# IOs_DMX8x8A.net
KiCad netlist of a schematic drawn in Altium Designer
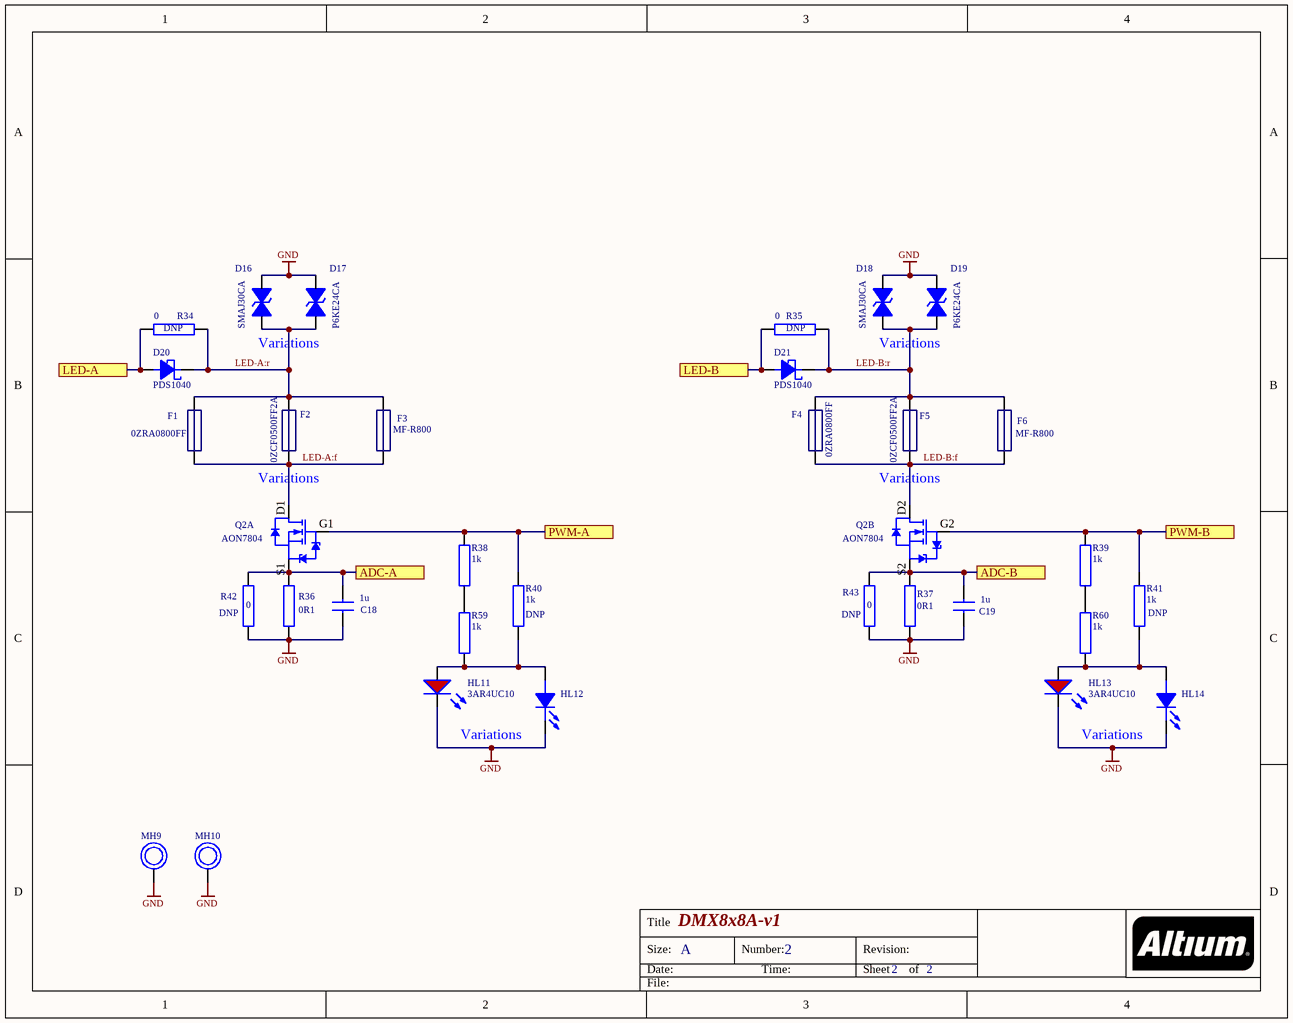
[diagram p0: IOs.DMX8x8A.SchDoc]

(export (version "E")
  (design (tool "Eeschema 10.0.6"))
  (components
    (comp (ref "C18")
      (value "1u")
      (footprint "Chip C 0402 - 1206")
      (description "Ceramic Chip Capacitor")
      (fields (field (name "Comment") "1u 50V 5%"))
      (libsource (lib "Capacitors") (part "Ceramic SMD Cap_R"))
    )
    (comp (ref "C19")
      (value "1u")
      (footprint "Chip C 0402 - 1206")
      (description "Ceramic Chip Capacitor")
      (fields (field (name "Comment") "1u 50V 5%"))
      (libsource (lib "Capacitors") (part "Ceramic SMD Cap_R"))
    )
    (comp (ref "D16")
      (value "SMAJ30CA")
      (footprint "DO-214AC (SMA) biplar")
      (description "TVS Uni 30V")
      (fields (field (name "MFR") "ST"))
      (libsource (lib "TVS") (part "SMAJ30CA"))
    )
    (comp (ref "D17")
      (value "P6KE24CA")
      (footprint "DIOAD1910W90L670D310 (DO-15)")
      (description "TVS Axial 600W Unipolar 24V")
      (libsource (lib "DMX512") (part "P6KE"))
    )
    (comp (ref "D18")
      (value "SMAJ30CA")
      (footprint "DO-214AC (SMA) biplar")
      (description "TVS Uni 30V")
      (fields (field (name "MFR") "ST"))
      (libsource (lib "TVS") (part "SMAJ30CA"))
    )
    (comp (ref "D19")
      (value "P6KE24CA")
      (footprint "DIOAD1910W90L670D310 (DO-15)")
      (description "TVS Axial 600W Unipolar 24V")
      (libsource (lib "DMX512") (part "P6KE"))
    )
    (comp (ref "D20")
      (value "PDS1040")
      (footprint "PDS1040")
      (description "10A SCHOTTKY BARRIER RECTIFIER")
      (fields (field (name "MFR") "DIODES INC."))
      (libsource (lib "Diodes") (part "PDS1040"))
    )
    (comp (ref "D21")
      (value "PDS1040")
      (footprint "PDS1040")
      (description "10A SCHOTTKY BARRIER RECTIFIER")
      (fields (field (name "MFR") "DIODES INC."))
      (libsource (lib "Diodes") (part "PDS1040"))
    )
    (comp (ref "F1")
      (value "0ZRA0800FF")
      (footprint "0ZRA0800FF")
      (description "Radial Leaded PTC 8/13.6A")
      (libsource (lib "DMX512") (part "0ZRA"))
    )
    (comp (ref "F2")
      (value "0ZCF0500FF2A")
      (footprint "0ZCF0500FF2A")
      (description "Surface Mount PTC 5/10A")
      (libsource (lib "DMX512") (part "0ZCF0500FF2A"))
    )
    (comp (ref "F3")
      (value "MF-R800")
      (footprint "MF-R800")
      (description "PTC Resettable Fuse 8/16A")
      (libsource (lib "DMX512") (part "MF-R800"))
    )
    (comp (ref "F4")
      (value "0ZRA0800FF")
      (footprint "0ZRA0800FF")
      (description "Radial Leaded PTC 8/13.6A")
      (libsource (lib "DMX512") (part "0ZRA"))
    )
    (comp (ref "F5")
      (value "0ZCF0500FF2A")
      (footprint "0ZCF0500FF2A")
      (description "Surface Mount PTC 5/10A")
      (libsource (lib "DMX512") (part "0ZCF0500FF2A"))
    )
    (comp (ref "F6")
      (value "MF-R800")
      (footprint "MF-R800")
      (description "PTC Resettable Fuse 8/16A")
      (libsource (lib "DMX512") (part "MF-R800"))
    )
    (comp (ref "HL11")
      (value "3AR4UC10")
      (footprint "LED-2pin 2.54mm")
      (description "LED 3mm Red")
      (libsource (lib "DMX512") (part "3AR4UC10"))
    )
    (comp (ref "HL12")
      (value "? Any")
      (footprint "LED SMD 0805")
      (description "LED 0805")
      (libsource (lib "DMX512") (part "LED 0805"))
    )
    (comp (ref "HL13")
      (value "3AR4UC10")
      (footprint "LED-2pin 2.54mm")
      (description "LED 3mm Red")
      (libsource (lib "DMX512") (part "3AR4UC10"))
    )
    (comp (ref "HL14")
      (value "? Any")
      (footprint "LED SMD 0805")
      (description "LED 0805")
      (libsource (lib "DMX512") (part "LED 0805"))
    )
    (comp (ref "MH9")
      (value "PMH")
      (footprint "Hole Pad 3.2x4mm")
      (description "Plated Mounting Hole")
      (libsource (lib "Misc") (part "PMH"))
    )
    (comp (ref "MH10")
      (value "PMH")
      (footprint "Hole Pad 3.2x4mm")
      (description "Plated Mounting Hole")
      (libsource (lib "Misc") (part "PMH"))
    )
    (comp (ref "Q2")
      (value "AON7804")
      (footprint "AON7804")
      (description "30V Dual N-Channel MOSFET")
      (libsource (lib "DMX512") (part "AON7804"))
    )
    (comp (ref "R34")
      (value "0")
      (footprint "Chip R 0402 - 1206")
      (description "Chip Resistor")
      (fields (field (name "DNP") "DNP") (field (name "Comment") "0 5%"))
      (libsource (lib "Resistors") (part "Chip R"))
    )
    (comp (ref "R35")
      (value "0")
      (footprint "Chip R 0402 - 1206")
      (description "Chip Resistor")
      (fields (field (name "DNP") "DNP") (field (name "Comment") "0 5%"))
      (libsource (lib "Resistors") (part "Chip R"))
    )
    (comp (ref "R36")
      (value "0R1")
      (footprint "DMX512:RES7W")
      (description "Resistor 7W Axial")
      (fields (field (name "MFR") "Yageo") (field (name "Comment") "KNP700JB-91-0R1"))
      (libsource (lib "DMX512") (part "Res 7W"))
    )
    (comp (ref "R37")
      (value "0R1")
      (footprint "DMX512:RES7W")
      (description "Resistor 7W Axial")
      (fields (field (name "MFR") "Yageo") (field (name "Comment") "KNP700JB-91-0R1"))
      (libsource (lib "DMX512") (part "Res 7W"))
    )
    (comp (ref "R38")
      (value "1k")
      (footprint "Chip R 0402 - 1206")
      (description "Chip Resistor")
      (fields (field (name "Comment") "1k 5%"))
      (libsource (lib "Resistors") (part "Chip R"))
    )
    (comp (ref "R39")
      (value "1k")
      (footprint "Chip R 0402 - 1206")
      (description "Chip Resistor")
      (fields (field (name "Comment") "1k 5%"))
      (libsource (lib "Resistors") (part "Chip R"))
    )
    (comp (ref "R40")
      (value "1k")
      (footprint "Chip R 0402 - 1206")
      (description "Chip Resistor")
      (fields (field (name "DNP") "DNP") (field (name "Comment") "1k 5%"))
      (libsource (lib "Resistors") (part "Chip R"))
    )
    (comp (ref "R41")
      (value "1k")
      (footprint "Chip R 0402 - 1206")
      (description "Chip Resistor")
      (fields (field (name "DNP") "DNP") (field (name "Comment") "1k 5%"))
      (libsource (lib "Resistors") (part "Chip R"))
    )
    (comp (ref "R42")
      (value "0")
      (footprint "Chip R 0402 - 1206")
      (description "Chip Resistor")
      (fields (field (name "DNP") "DNP") (field (name "Comment") "0 5%"))
      (libsource (lib "Resistors") (part "Chip R"))
    )
    (comp (ref "R43")
      (value "0")
      (footprint "Chip R 0402 - 1206")
      (description "Chip Resistor")
      (fields (field (name "DNP") "DNP") (field (name "Comment") "0 5%"))
      (libsource (lib "Resistors") (part "Chip R"))
    )
    (comp (ref "R59")
      (value "1k")
      (footprint "Chip R 0402 - 1206")
      (description "Chip Resistor")
      (fields (field (name "Comment") "1k 5%"))
      (libsource (lib "Resistors") (part "Chip R"))
    )
    (comp (ref "R60")
      (value "1k")
      (footprint "Chip R 0402 - 1206")
      (description "Chip Resistor")
      (fields (field (name "Comment") "1k 5%"))
      (libsource (lib "Resistors") (part "Chip R"))
    )
  )
  (nets
    (net (code "1") (name "/ADC-A") (class "Default")
      (node (ref "C18") (pin "2") (pinfunction "2_2") (pintype "passive"))
      (node (ref "Q2") (pin "S1") (pinfunction "S1_S1") (pintype "passive"))
      (node (ref "R36") (pin "2") (pinfunction "2_2") (pintype "passive"))
      (node (ref "R42") (pin "2") (pinfunction "2_2") (pintype "passive"))
    )
    (net (code "2") (name "/ADC-B") (class "Default")
      (node (ref "C19") (pin "2") (pinfunction "2_2") (pintype "passive"))
      (node (ref "Q2") (pin "S2") (pinfunction "S1_S2") (pintype "passive"))
      (node (ref "R37") (pin "2") (pinfunction "2_2") (pintype "passive"))
      (node (ref "R43") (pin "2") (pinfunction "2_2") (pintype "passive"))
    )
    (net (code "3") (name "/LED-A") (class "Default")
      (node (ref "D20") (pin "1") (pinfunction "A_1") (pintype "passive"))
      (node (ref "R34") (pin "2") (pinfunction "2_2") (pintype "passive"))
    )
    (net (code "4") (name "/LED-A:f") (class "Default")
      (node (ref "F1") (pin "1") (pinfunction "1_1") (pintype "passive"))
      (node (ref "F2") (pin "1") (pinfunction "1_1") (pintype "passive"))
      (node (ref "F3") (pin "1") (pinfunction "1_1") (pintype "passive"))
      (node (ref "Q2") (pin "D1") (pinfunction "D1_D1") (pintype "passive"))
    )
    (net (code "5") (name "/LED-A:r") (class "Default")
      (node (ref "D16") (pin "2") (pinfunction "2_2") (pintype "passive"))
      (node (ref "D17") (pin "2") (pinfunction "2_2") (pintype "passive"))
      (node (ref "D20") (pin "2") (pinfunction "K_2") (pintype "passive"))
      (node (ref "F1") (pin "2") (pinfunction "2_2") (pintype "passive"))
      (node (ref "F2") (pin "2") (pinfunction "2_2") (pintype "passive"))
      (node (ref "F3") (pin "2") (pinfunction "2_2") (pintype "passive"))
      (node (ref "R34") (pin "1") (pinfunction "1_1") (pintype "passive"))
    )
    (net (code "6") (name "/LED-B") (class "Default")
      (node (ref "D21") (pin "1") (pinfunction "A_1") (pintype "passive"))
      (node (ref "R35") (pin "2") (pinfunction "2_2") (pintype "passive"))
    )
    (net (code "7") (name "/LED-B:f") (class "Default")
      (node (ref "F4") (pin "1") (pinfunction "1_1") (pintype "passive"))
      (node (ref "F5") (pin "1") (pinfunction "1_1") (pintype "passive"))
      (node (ref "F6") (pin "1") (pinfunction "1_1") (pintype "passive"))
      (node (ref "Q2") (pin "D2") (pinfunction "D2_D2") (pintype "passive"))
    )
    (net (code "8") (name "/LED-B:r") (class "Default")
      (node (ref "D18") (pin "2") (pinfunction "2_2") (pintype "passive"))
      (node (ref "D19") (pin "2") (pinfunction "2_2") (pintype "passive"))
      (node (ref "D21") (pin "2") (pinfunction "K_2") (pintype "passive"))
      (node (ref "F4") (pin "2") (pinfunction "2_2") (pintype "passive"))
      (node (ref "F5") (pin "2") (pinfunction "2_2") (pintype "passive"))
      (node (ref "F6") (pin "2") (pinfunction "2_2") (pintype "passive"))
      (node (ref "R35") (pin "1") (pinfunction "1_1") (pintype "passive"))
    )
    (net (code "9") (name "/PWM-A") (class "Default")
      (node (ref "Q2") (pin "G1") (pinfunction "G1_G1") (pintype "passive"))
      (node (ref "R38") (pin "1") (pinfunction "1_1") (pintype "passive"))
      (node (ref "R40") (pin "1") (pinfunction "1_1") (pintype "passive"))
    )
    (net (code "10") (name "/PWM-B") (class "Default")
      (node (ref "Q2") (pin "G2") (pinfunction "G1_G2") (pintype "passive"))
      (node (ref "R39") (pin "1") (pinfunction "1_1") (pintype "passive"))
      (node (ref "R41") (pin "1") (pinfunction "1_1") (pintype "passive"))
    )
    (net (code "11") (name "GND") (class "Default")
      (node (ref "C18") (pin "1") (pinfunction "1_1") (pintype "passive"))
      (node (ref "C19") (pin "1") (pinfunction "1_1") (pintype "passive"))
      (node (ref "D16") (pin "1") (pinfunction "1_1") (pintype "passive"))
      (node (ref "D17") (pin "1") (pinfunction "1_1") (pintype "passive"))
      (node (ref "D18") (pin "1") (pinfunction "1_1") (pintype "passive"))
      (node (ref "D19") (pin "1") (pinfunction "1_1") (pintype "passive"))
      (node (ref "HL11") (pin "2") (pinfunction "2_2") (pintype "passive"))
      (node (ref "HL12") (pin "2") (pinfunction "K_2") (pintype "passive"))
      (node (ref "HL13") (pin "2") (pinfunction "2_2") (pintype "passive"))
      (node (ref "HL14") (pin "2") (pinfunction "K_2") (pintype "passive"))
      (node (ref "MH10") (pin "1") (pinfunction "1_1") (pintype "passive"))
      (node (ref "MH9") (pin "1") (pinfunction "1_1") (pintype "passive"))
      (node (ref "R36") (pin "1") (pinfunction "1_1") (pintype "passive"))
      (node (ref "R37") (pin "1") (pinfunction "1_1") (pintype "passive"))
      (node (ref "R42") (pin "1") (pinfunction "1_1") (pintype "passive"))
      (node (ref "R43") (pin "1") (pinfunction "1_1") (pintype "passive"))
    )
    (net (code "12") (name "Net-(HL12-A)") (class "Default")
      (node (ref "HL11") (pin "1") (pinfunction "1_1") (pintype "passive"))
      (node (ref "HL12") (pin "1") (pinfunction "A_1") (pintype "passive"))
      (node (ref "R40") (pin "2") (pinfunction "2_2") (pintype "passive"))
      (node (ref "R59") (pin "2") (pinfunction "2_2") (pintype "passive"))
    )
    (net (code "13") (name "Net-(HL14-A)") (class "Default")
      (node (ref "HL13") (pin "1") (pinfunction "1_1") (pintype "passive"))
      (node (ref "HL14") (pin "1") (pinfunction "A_1") (pintype "passive"))
      (node (ref "R41") (pin "2") (pinfunction "2_2") (pintype "passive"))
      (node (ref "R60") (pin "2") (pinfunction "2_2") (pintype "passive"))
    )
    (net (code "14") (name "Net-(R38-Pad2)") (class "Default")
      (node (ref "R38") (pin "2") (pinfunction "2_2") (pintype "passive"))
      (node (ref "R59") (pin "1") (pinfunction "1_1") (pintype "passive"))
    )
    (net (code "15") (name "Net-(R39-Pad2)") (class "Default")
      (node (ref "R39") (pin "2") (pinfunction "2_2") (pintype "passive"))
      (node (ref "R60") (pin "1") (pinfunction "1_1") (pintype "passive"))
    )
  )
)
